# Shutter_Sensors_Old.net
KiCad netlist of a schematic drawn in EAGLE
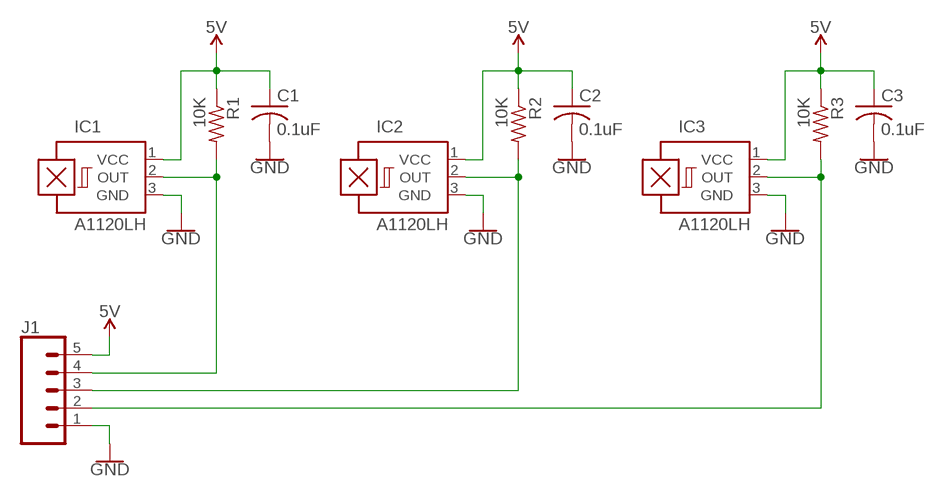
[diagram p0: schematic, sheet 1]

(export (version "E")
  (design (tool "Eeschema 10.0.6"))
  (components
    (comp (ref "C1")
      (value "0.1uF")
      (footprint "eagle-import:C0805")
      (libsource (lib "eagle-import") (part "C-USC0805"))
    )
    (comp (ref "C2")
      (value "0.1uF")
      (footprint "eagle-import:C0805")
      (libsource (lib "eagle-import") (part "C-USC0805"))
    )
    (comp (ref "C3")
      (value "0.1uF")
      (footprint "eagle-import:C0805")
      (libsource (lib "eagle-import") (part "C-USC0805"))
    )
    (comp (ref "IC1")
      (value "A1120LH")
      (footprint "eagle-import:SOT23-W")
      (fields (field (name "MF") "ALLEGRO MICROSYSTEMS, INC.") (field (name "MPN") "A1203LLHLT-T"))
      (libsource (lib "eagle-import") (part "A12?LH03"))
    )
    (comp (ref "IC2")
      (value "A1120LH")
      (footprint "eagle-import:SOT23-W")
      (fields (field (name "MF") "ALLEGRO MICROSYSTEMS, INC.") (field (name "MPN") "A1203LLHLT-T"))
      (libsource (lib "eagle-import") (part "A12?LH03"))
    )
    (comp (ref "IC3")
      (value "A1120LH")
      (footprint "eagle-import:SOT23-W")
      (fields (field (name "MF") "ALLEGRO MICROSYSTEMS, INC.") (field (name "MPN") "A1203LLHLT-T"))
      (libsource (lib "eagle-import") (part "A12?LH03"))
    )
    (comp (ref "J1")
      (value "CONN_05")
      (footprint "eagle-import:1X05")
      (libsource (lib "eagle-import") (part "CONN_05"))
    )
    (comp (ref "R1")
      (value "10K")
      (footprint "eagle-import:R0805")
      (libsource (lib "eagle-import") (part "R-US_R0805"))
    )
    (comp (ref "R2")
      (value "10K")
      (footprint "eagle-import:R0805")
      (libsource (lib "eagle-import") (part "R-US_R0805"))
    )
    (comp (ref "R3")
      (value "10K")
      (footprint "eagle-import:R0805")
      (libsource (lib "eagle-import") (part "R-US_R0805"))
    )
  )
  (nets
    (net (code "1") (name "5V") (class "Default")
      (node (ref "C1") (pin "1") (pinfunction "1_1") (pintype "passive"))
      (node (ref "C2") (pin "1") (pinfunction "1_1") (pintype "passive"))
      (node (ref "C3") (pin "1") (pinfunction "1_1") (pintype "passive"))
      (node (ref "IC1") (pin "1") (pinfunction "VCC_1") (pintype "power_in"))
      (node (ref "IC2") (pin "1") (pinfunction "VCC_1") (pintype "power_in"))
      (node (ref "IC3") (pin "1") (pinfunction "VCC_1") (pintype "power_in"))
      (node (ref "J1") (pin "5") (pinfunction "5_5") (pintype "passive"))
      (node (ref "R1") (pin "1") (pinfunction "1_1") (pintype "passive"))
      (node (ref "R2") (pin "1") (pinfunction "1_1") (pintype "passive"))
      (node (ref "R3") (pin "1") (pinfunction "1_1") (pintype "passive"))
    )
    (net (code "2") (name "GND") (class "Default")
      (node (ref "C1") (pin "2") (pinfunction "2_2") (pintype "passive"))
      (node (ref "C2") (pin "2") (pinfunction "2_2") (pintype "passive"))
      (node (ref "C3") (pin "2") (pinfunction "2_2") (pintype "passive"))
      (node (ref "IC1") (pin "3") (pinfunction "GND_3") (pintype "power_in"))
      (node (ref "IC2") (pin "3") (pinfunction "GND_3") (pintype "power_in"))
      (node (ref "IC3") (pin "3") (pinfunction "GND_3") (pintype "power_in"))
      (node (ref "J1") (pin "1") (pinfunction "1_1") (pintype "passive"))
    )
    (net (code "3") (name "Net-(IC1-OUT)") (class "Default")
      (node (ref "IC1") (pin "2") (pinfunction "OUT_2") (pintype "output"))
      (node (ref "J1") (pin "4") (pinfunction "4_4") (pintype "passive"))
      (node (ref "R1") (pin "2") (pinfunction "2_2") (pintype "passive"))
    )
    (net (code "4") (name "Net-(IC2-OUT)") (class "Default")
      (node (ref "IC2") (pin "2") (pinfunction "OUT_2") (pintype "output"))
      (node (ref "J1") (pin "3") (pinfunction "3_3") (pintype "passive"))
      (node (ref "R2") (pin "2") (pinfunction "2_2") (pintype "passive"))
    )
    (net (code "5") (name "Net-(IC3-OUT)") (class "Default")
      (node (ref "IC3") (pin "2") (pinfunction "OUT_2") (pintype "output"))
      (node (ref "J1") (pin "2") (pinfunction "2_2") (pintype "passive"))
      (node (ref "R3") (pin "2") (pinfunction "2_2") (pintype "passive"))
    )
  )
)
